# IMU.net
KiCad netlist of a schematic drawn in Altium Designer
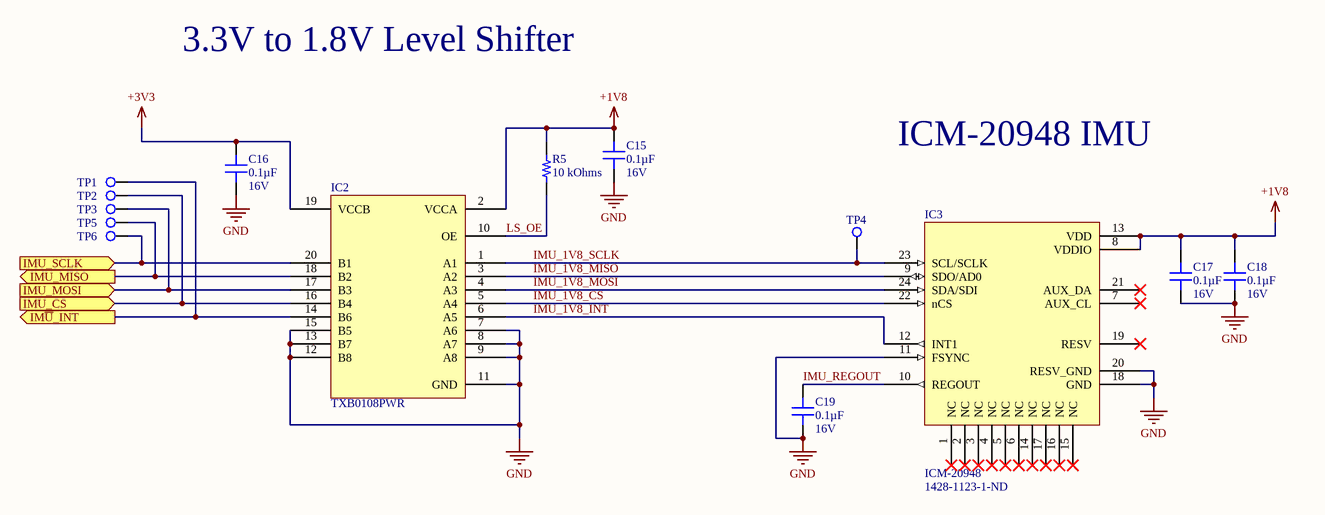
[diagram p0: IMU.SchDoc]

(export (version "E")
  (design (tool "Eeschema 10.0.6"))
  (components
    (comp (ref "C15")
      (value "0.1µF")
      (footprint "CAP 0603_1608")
      (description "CAP CER 0.1UF 16V X7R 0603")
      (fields
        (field (name "PART NUMBER") "CC0603KRX7R7BB104")
        (field (name "MANUFACTURER") "Yageo")
        (field (name "VOLTAGE - RATED") "16V")
      )
      (libsource (lib "Celestial Altium Library - altium_library") (part "Capacitor"))
    )
    (comp (ref "C16")
      (value "0.1µF")
      (footprint "CAP 0603_1608")
      (description "CAP CER 0.1UF 16V X7R 0603")
      (fields
        (field (name "PART NUMBER") "CC0603KRX7R7BB104")
        (field (name "MANUFACTURER") "Yageo")
        (field (name "VOLTAGE - RATED") "16V")
      )
      (libsource (lib "Celestial Altium Library - altium_library") (part "Capacitor"))
    )
    (comp (ref "C17")
      (value "0.1µF")
      (footprint "CAP 0603_1608")
      (description "CAP CER 0.1UF 16V X7R 0603")
      (fields
        (field (name "PART NUMBER") "CC0603KRX7R7BB104")
        (field (name "MANUFACTURER") "Yageo")
        (field (name "VOLTAGE - RATED") "16V")
      )
      (libsource (lib "Celestial Altium Library - altium_library") (part "Capacitor"))
    )
    (comp (ref "C18")
      (value "0.1µF")
      (footprint "CAP 0603_1608")
      (description "CAP CER 0.1UF 16V X7R 0603")
      (fields
        (field (name "PART NUMBER") "CC0603KRX7R7BB104")
        (field (name "MANUFACTURER") "Yageo")
        (field (name "VOLTAGE - RATED") "16V")
      )
      (libsource (lib "Celestial Altium Library - altium_library") (part "Capacitor"))
    )
    (comp (ref "C19")
      (value "0.1µF")
      (footprint "CAP 0603_1608")
      (description "CAP CER 0.1UF 16V X7R 0603")
      (fields
        (field (name "PART NUMBER") "CC0603KRX7R7BB104")
        (field (name "MANUFACTURER") "Yageo")
        (field (name "VOLTAGE - RATED") "16V")
      )
      (libsource (lib "Celestial Altium Library - altium_library") (part "Capacitor"))
    )
    (comp (ref "IC2")
      (value "TXB0108PWR")
      (footprint "TI TSSOP-20 PW")
      (description "IC TRNSLTR BIDIRECTIONAL 20TSSOP")
      (fields (field (name "MANUFACTURER") "Texas Instruments"))
      (libsource (lib "Celestial Altium Library - altium_library") (part "TI TXB0108PWR"))
    )
    (comp (ref "IC3")
      (value "ICM-20948")
      (footprint "ICM-20948")
      (description "Accelerometer, Gyroscope, Magnetometer, 9 Axis Sensor I²C, SPI Output")
      (fields
        (field (name "SUPPLIER PART NUMBER 1") "1428-1123-1-ND")
        (field (name "COPYRIGHT") "Copyright (C) 2018 Accelerated Designs. All rights reserved")
      )
      (libsource (lib "Drone") (part "ICM-20948"))
    )
    (comp (ref "R5")
      (value "10 kOhms")
      (footprint "RES 0603_1608")
      (description "RES SMD 10K OHM 1% 1/10W 0603")
      (fields (field (name "PART NUMBER") "AC0603FR-0710KL") (field (name "MANUFACTURER") "Yageo"))
      (libsource (lib "Celestial Altium Library - altium_library") (part "Resistor"))
    )
    (comp (ref "TP1")
      (value "TestPoint")
      (footprint "TestPoint")
      (libsource (lib "Drone") (part "TestPoint"))
    )
    (comp (ref "TP2")
      (value "TestPoint")
      (footprint "TestPoint")
      (libsource (lib "Drone") (part "TestPoint"))
    )
    (comp (ref "TP3")
      (value "TestPoint")
      (footprint "TestPoint")
      (libsource (lib "Drone") (part "TestPoint"))
    )
    (comp (ref "TP4")
      (value "TestPoint")
      (footprint "TestPoint")
      (libsource (lib "Drone") (part "TestPoint"))
    )
    (comp (ref "TP5")
      (value "TestPoint")
      (footprint "TestPoint")
      (libsource (lib "Drone") (part "TestPoint"))
    )
    (comp (ref "TP6")
      (value "TestPoint")
      (footprint "TestPoint")
      (libsource (lib "Drone") (part "TestPoint"))
    )
  )
  (nets
    (net (code "1") (name "+1V8") (class "Default")
      (node (ref "C15") (pin "1") (pinfunction "1_1") (pintype "passive"))
      (node (ref "C17") (pin "2") (pinfunction "2_2") (pintype "passive"))
      (node (ref "C18") (pin "2") (pinfunction "2_2") (pintype "passive"))
      (node (ref "IC2") (pin "2") (pinfunction "VCCA_2") (pintype "passive"))
      (node (ref "IC3") (pin "13") (pinfunction "VDD_13") (pintype "power_in"))
      (node (ref "IC3") (pin "8") (pinfunction "VDDIO_8") (pintype "power_in"))
      (node (ref "R5") (pin "1") (pinfunction "1_1") (pintype "passive"))
    )
    (net (code "2") (name "+3V3") (class "Default")
      (node (ref "C16") (pin "2") (pinfunction "2_2") (pintype "passive"))
      (node (ref "IC2") (pin "19") (pinfunction "VCCB_19") (pintype "passive"))
    )
    (net (code "3") (name "/IMU_1V8_CS") (class "Default")
      (node (ref "IC2") (pin "5") (pinfunction "A4_5") (pintype "passive"))
      (node (ref "IC3") (pin "22") (pinfunction "nCS_22") (pintype "input"))
    )
    (net (code "4") (name "/IMU_1V8_INT") (class "Default")
      (node (ref "IC2") (pin "6") (pinfunction "A5_6") (pintype "passive"))
      (node (ref "IC3") (pin "12") (pinfunction "INT1_12") (pintype "output"))
    )
    (net (code "5") (name "/IMU_1V8_MISO") (class "Default")
      (node (ref "IC2") (pin "3") (pinfunction "A2_3") (pintype "passive"))
      (node (ref "IC3") (pin "9") (pinfunction "SDO/AD0_9") (pintype "bidirectional"))
    )
    (net (code "6") (name "/IMU_1V8_MOSI") (class "Default")
      (node (ref "IC2") (pin "4") (pinfunction "A3_4") (pintype "passive"))
      (node (ref "IC3") (pin "24") (pinfunction "SDA/SDI_24") (pintype "input"))
    )
    (net (code "7") (name "/IMU_1V8_SCLK") (class "Default")
      (node (ref "IC2") (pin "1") (pinfunction "A1_1") (pintype "passive"))
      (node (ref "IC3") (pin "23") (pinfunction "SCL/SCLK_23") (pintype "input"))
      (node (ref "TP4") (pin "1") (pinfunction "1_1") (pintype "passive"))
    )
    (net (code "8") (name "/IMU_CS") (class "Default")
      (node (ref "IC2") (pin "16") (pinfunction "B4_16") (pintype "passive"))
      (node (ref "TP2") (pin "1") (pinfunction "1_1") (pintype "passive"))
    )
    (net (code "9") (name "/IMU_MISO") (class "Default")
      (node (ref "IC2") (pin "18") (pinfunction "B2_18") (pintype "passive"))
      (node (ref "TP5") (pin "1") (pinfunction "1_1") (pintype "passive"))
    )
    (net (code "10") (name "/IMU_MOSI") (class "Default")
      (node (ref "IC2") (pin "17") (pinfunction "B3_17") (pintype "passive"))
      (node (ref "TP3") (pin "1") (pinfunction "1_1") (pintype "passive"))
    )
    (net (code "11") (name "/IMU_REGOUT") (class "Default")
      (node (ref "C19") (pin "2") (pinfunction "2_2") (pintype "passive"))
      (node (ref "IC3") (pin "10") (pinfunction "REGOUT_10") (pintype "output"))
    )
    (net (code "12") (name "/IMU_SCLK") (class "Default")
      (node (ref "IC2") (pin "20") (pinfunction "B1_20") (pintype "passive"))
      (node (ref "TP6") (pin "1") (pinfunction "1_1") (pintype "passive"))
    )
    (net (code "13") (name "/IM~{U}_INT") (class "Default")
      (node (ref "IC2") (pin "14") (pinfunction "B6_14") (pintype "passive"))
      (node (ref "TP1") (pin "1") (pinfunction "1_1") (pintype "passive"))
    )
    (net (code "14") (name "/LS_OE") (class "Default")
      (node (ref "IC2") (pin "10") (pinfunction "OE_10") (pintype "passive"))
      (node (ref "R5") (pin "2") (pinfunction "2_2") (pintype "passive"))
    )
    (net (code "15") (name "GND") (class "Default")
      (node (ref "C15") (pin "2") (pinfunction "2_2") (pintype "passive"))
      (node (ref "C16") (pin "1") (pinfunction "1_1") (pintype "passive"))
      (node (ref "C17") (pin "1") (pinfunction "1_1") (pintype "passive"))
      (node (ref "C18") (pin "1") (pinfunction "1_1") (pintype "passive"))
      (node (ref "C19") (pin "1") (pinfunction "1_1") (pintype "passive"))
      (node (ref "IC2") (pin "11") (pinfunction "GND_11") (pintype "passive"))
      (node (ref "IC2") (pin "12") (pinfunction "B8_12") (pintype "passive"))
      (node (ref "IC2") (pin "13") (pinfunction "B7_13") (pintype "passive"))
      (node (ref "IC2") (pin "15") (pinfunction "B5_15") (pintype "passive"))
      (node (ref "IC2") (pin "7") (pinfunction "A6_7") (pintype "passive"))
      (node (ref "IC2") (pin "8") (pinfunction "A7_8") (pintype "passive"))
      (node (ref "IC2") (pin "9") (pinfunction "A8_9") (pintype "passive"))
      (node (ref "IC3") (pin "11") (pinfunction "FSYNC_11") (pintype "input"))
      (node (ref "IC3") (pin "18") (pinfunction "GND_18") (pintype "passive"))
      (node (ref "IC3") (pin "20") (pinfunction "RESV_GND_20") (pintype "passive"))
    )
    (net (code "16") (name "unconnected-(IC3-AUX_CL-Pad7)") (class "Default")
      (node (ref "IC3") (pin "7") (pinfunction "AUX_CL_7") (pintype "passive+no_connect"))
    )
    (net (code "17") (name "unconnected-(IC3-AUX_DA-Pad21)") (class "Default")
      (node (ref "IC3") (pin "21") (pinfunction "AUX_DA_21") (pintype "passive+no_connect"))
    )
    (net (code "18") (name "unconnected-(IC3-NC-Pad1)") (class "Default")
      (node (ref "IC3") (pin "1") (pinfunction "NC_1") (pintype "passive+no_connect"))
    )
    (net (code "19") (name "unconnected-(IC3-NC-Pad2)") (class "Default")
      (node (ref "IC3") (pin "2") (pinfunction "NC_2") (pintype "passive+no_connect"))
    )
    (net (code "20") (name "unconnected-(IC3-NC-Pad3)") (class "Default")
      (node (ref "IC3") (pin "3") (pinfunction "NC_3") (pintype "passive+no_connect"))
    )
    (net (code "21") (name "unconnected-(IC3-NC-Pad4)") (class "Default")
      (node (ref "IC3") (pin "4") (pinfunction "NC_4") (pintype "passive+no_connect"))
    )
    (net (code "22") (name "unconnected-(IC3-NC-Pad5)") (class "Default")
      (node (ref "IC3") (pin "5") (pinfunction "NC_5") (pintype "passive+no_connect"))
    )
    (net (code "23") (name "unconnected-(IC3-NC-Pad6)") (class "Default")
      (node (ref "IC3") (pin "6") (pinfunction "NC_6") (pintype "passive+no_connect"))
    )
    (net (code "24") (name "unconnected-(IC3-NC-Pad14)") (class "Default")
      (node (ref "IC3") (pin "14") (pinfunction "NC_14") (pintype "passive+no_connect"))
    )
    (net (code "25") (name "unconnected-(IC3-NC-Pad15)") (class "Default")
      (node (ref "IC3") (pin "15") (pinfunction "NC_15") (pintype "passive+no_connect"))
    )
    (net (code "26") (name "unconnected-(IC3-NC-Pad16)") (class "Default")
      (node (ref "IC3") (pin "16") (pinfunction "NC_16") (pintype "passive+no_connect"))
    )
    (net (code "27") (name "unconnected-(IC3-NC-Pad17)") (class "Default")
      (node (ref "IC3") (pin "17") (pinfunction "NC_17") (pintype "passive+no_connect"))
    )
    (net (code "28") (name "unconnected-(IC3-RESV-Pad19)") (class "Default")
      (node (ref "IC3") (pin "19") (pinfunction "RESV_19") (pintype "passive+no_connect"))
    )
  )
)
